# Master_MicroController_Port_C.net
KiCad netlist of a schematic drawn in Altium Designer
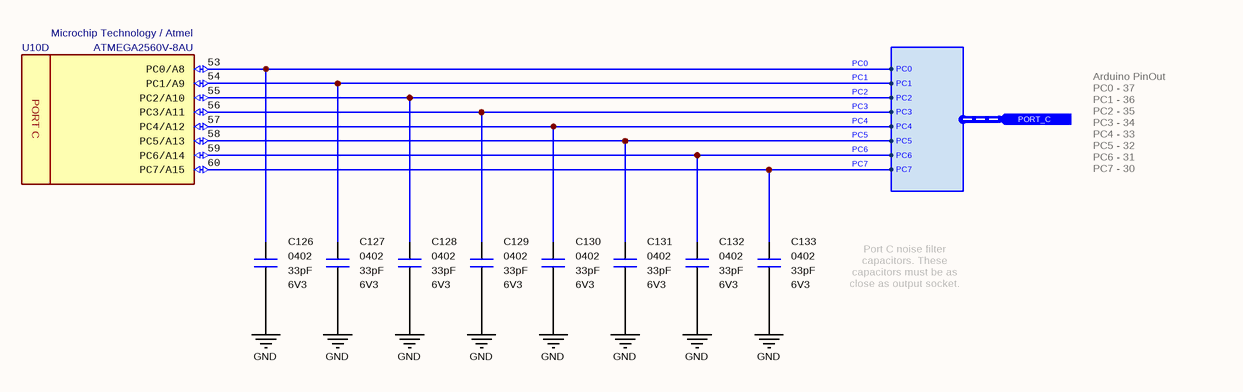
[diagram p0: Master MicroController Port C.SchDoc]

(export (version "E")
  (design (tool "Eeschema 10.0.6"))
  (components
    (comp (ref "C126")
      (value "33pF")
      (footprint "CAPACITOR_0402")
      (description "Capacitor - 33pF [0402] (Ceramic)")
      (fields
        (field (name "TOLERANCE") "10%")
        (field (name "CASE") "0402")
        (field (name "VOLTAGE") "6V3")
        (field (name "MANUFACTURER PART NUMBER") "C0402C330J9RACAUTO")
      )
      (libsource (lib "Ovoo_Library") (part "Capacitor - 33pF [0402-6V3]"))
    )
    (comp (ref "C127")
      (value "33pF")
      (footprint "CAPACITOR_0402")
      (description "Capacitor - 33pF [0402] (Ceramic)")
      (fields
        (field (name "TOLERANCE") "10%")
        (field (name "CASE") "0402")
        (field (name "VOLTAGE") "6V3")
        (field (name "MANUFACTURER PART NUMBER") "C0402C330J9RACAUTO")
      )
      (libsource (lib "Ovoo_Library") (part "Capacitor - 33pF [0402-6V3]"))
    )
    (comp (ref "C128")
      (value "33pF")
      (footprint "CAPACITOR_0402")
      (description "Capacitor - 33pF [0402] (Ceramic)")
      (fields
        (field (name "TOLERANCE") "10%")
        (field (name "CASE") "0402")
        (field (name "VOLTAGE") "6V3")
        (field (name "MANUFACTURER PART NUMBER") "C0402C330J9RACAUTO")
      )
      (libsource (lib "Ovoo_Library") (part "Capacitor - 33pF [0402-6V3]"))
    )
    (comp (ref "C129")
      (value "33pF")
      (footprint "CAPACITOR_0402")
      (description "Capacitor - 33pF [0402] (Ceramic)")
      (fields
        (field (name "TOLERANCE") "10%")
        (field (name "CASE") "0402")
        (field (name "VOLTAGE") "6V3")
        (field (name "MANUFACTURER PART NUMBER") "C0402C330J9RACAUTO")
      )
      (libsource (lib "Ovoo_Library") (part "Capacitor - 33pF [0402-6V3]"))
    )
    (comp (ref "C130")
      (value "33pF")
      (footprint "CAPACITOR_0402")
      (description "Capacitor - 33pF [0402] (Ceramic)")
      (fields
        (field (name "TOLERANCE") "10%")
        (field (name "CASE") "0402")
        (field (name "VOLTAGE") "6V3")
        (field (name "MANUFACTURER PART NUMBER") "C0402C330J9RACAUTO")
      )
      (libsource (lib "Ovoo_Library") (part "Capacitor - 33pF [0402-6V3]"))
    )
    (comp (ref "C131")
      (value "33pF")
      (footprint "CAPACITOR_0402")
      (description "Capacitor - 33pF [0402] (Ceramic)")
      (fields
        (field (name "TOLERANCE") "10%")
        (field (name "CASE") "0402")
        (field (name "VOLTAGE") "6V3")
        (field (name "MANUFACTURER PART NUMBER") "C0402C330J9RACAUTO")
      )
      (libsource (lib "Ovoo_Library") (part "Capacitor - 33pF [0402-6V3]"))
    )
    (comp (ref "C132")
      (value "33pF")
      (footprint "CAPACITOR_0402")
      (description "Capacitor - 33pF [0402] (Ceramic)")
      (fields
        (field (name "TOLERANCE") "10%")
        (field (name "CASE") "0402")
        (field (name "VOLTAGE") "6V3")
        (field (name "MANUFACTURER PART NUMBER") "C0402C330J9RACAUTO")
      )
      (libsource (lib "Ovoo_Library") (part "Capacitor - 33pF [0402-6V3]"))
    )
    (comp (ref "C133")
      (value "33pF")
      (footprint "CAPACITOR_0402")
      (description "Capacitor - 33pF [0402] (Ceramic)")
      (fields
        (field (name "TOLERANCE") "10%")
        (field (name "CASE") "0402")
        (field (name "VOLTAGE") "6V3")
        (field (name "MANUFACTURER PART NUMBER") "C0402C330J9RACAUTO")
      )
      (libsource (lib "Ovoo_Library") (part "Capacitor - 33pF [0402-6V3]"))
    )
    (comp (ref "U10")
      (value "8-bit MicroController")
      (footprint "TQFP100")
      (description "8-bit Microcontrollers - MCU 256kB Flash 4kB EEPROM 86 I/O Pins")
      (fields
        (field (name "MANUFACTURER PART NUMBER") "ATMEGA2560V-8AU")
        (field (name "MANUFACTURER NAME") "Microchip Technology / Atmel")
      )
      (libsource (lib "Ovoo_Library") (part "IC - ATMEGA2560V-8AU"))
    )
  )
  (nets
    (net (code "2") (name "/PC0") (class "Default")
      (node (ref "C126") (pin "2") (pinfunction "2_2") (pintype "passive"))
      (node (ref "U10") (pin "53") (pinfunction "PC0/A8_53") (pintype "bidirectional"))
    )
    (net (code "3") (name "/PC1") (class "Default")
      (node (ref "C127") (pin "2") (pinfunction "2_2") (pintype "passive"))
      (node (ref "U10") (pin "54") (pinfunction "PC1/A9_54") (pintype "bidirectional"))
    )
    (net (code "4") (name "/PC2") (class "Default")
      (node (ref "C128") (pin "2") (pinfunction "2_2") (pintype "passive"))
      (node (ref "U10") (pin "55") (pinfunction "PC2/A10_55") (pintype "bidirectional"))
    )
    (net (code "5") (name "/PC3") (class "Default")
      (node (ref "C129") (pin "2") (pinfunction "2_2") (pintype "passive"))
      (node (ref "U10") (pin "56") (pinfunction "PC3/A11_56") (pintype "bidirectional"))
    )
    (net (code "6") (name "/PC4") (class "Default")
      (node (ref "C130") (pin "2") (pinfunction "2_2") (pintype "passive"))
      (node (ref "U10") (pin "57") (pinfunction "PC4/A12_57") (pintype "bidirectional"))
    )
    (net (code "7") (name "/PC5") (class "Default")
      (node (ref "C131") (pin "2") (pinfunction "2_2") (pintype "passive"))
      (node (ref "U10") (pin "58") (pinfunction "PC5/A13_58") (pintype "bidirectional"))
    )
    (net (code "8") (name "/PC6") (class "Default")
      (node (ref "C132") (pin "2") (pinfunction "2_2") (pintype "passive"))
      (node (ref "U10") (pin "59") (pinfunction "PC6/A14_59") (pintype "bidirectional"))
    )
    (net (code "9") (name "/PC7") (class "Default")
      (node (ref "C133") (pin "2") (pinfunction "2_2") (pintype "passive"))
      (node (ref "U10") (pin "60") (pinfunction "PC7/A15_60") (pintype "bidirectional"))
    )
    (net (code "11") (name "GND") (class "Default")
      (node (ref "C126") (pin "1") (pinfunction "1_1") (pintype "passive"))
      (node (ref "C127") (pin "1") (pinfunction "1_1") (pintype "passive"))
      (node (ref "C128") (pin "1") (pinfunction "1_1") (pintype "passive"))
      (node (ref "C129") (pin "1") (pinfunction "1_1") (pintype "passive"))
      (node (ref "C130") (pin "1") (pinfunction "1_1") (pintype "passive"))
      (node (ref "C131") (pin "1") (pinfunction "1_1") (pintype "passive"))
      (node (ref "C132") (pin "1") (pinfunction "1_1") (pintype "passive"))
      (node (ref "C133") (pin "1") (pinfunction "1_1") (pintype "passive"))
    )
  )
)
